# SparkX-Pi-Filter.net
KiCad netlist of a schematic drawn in EAGLE
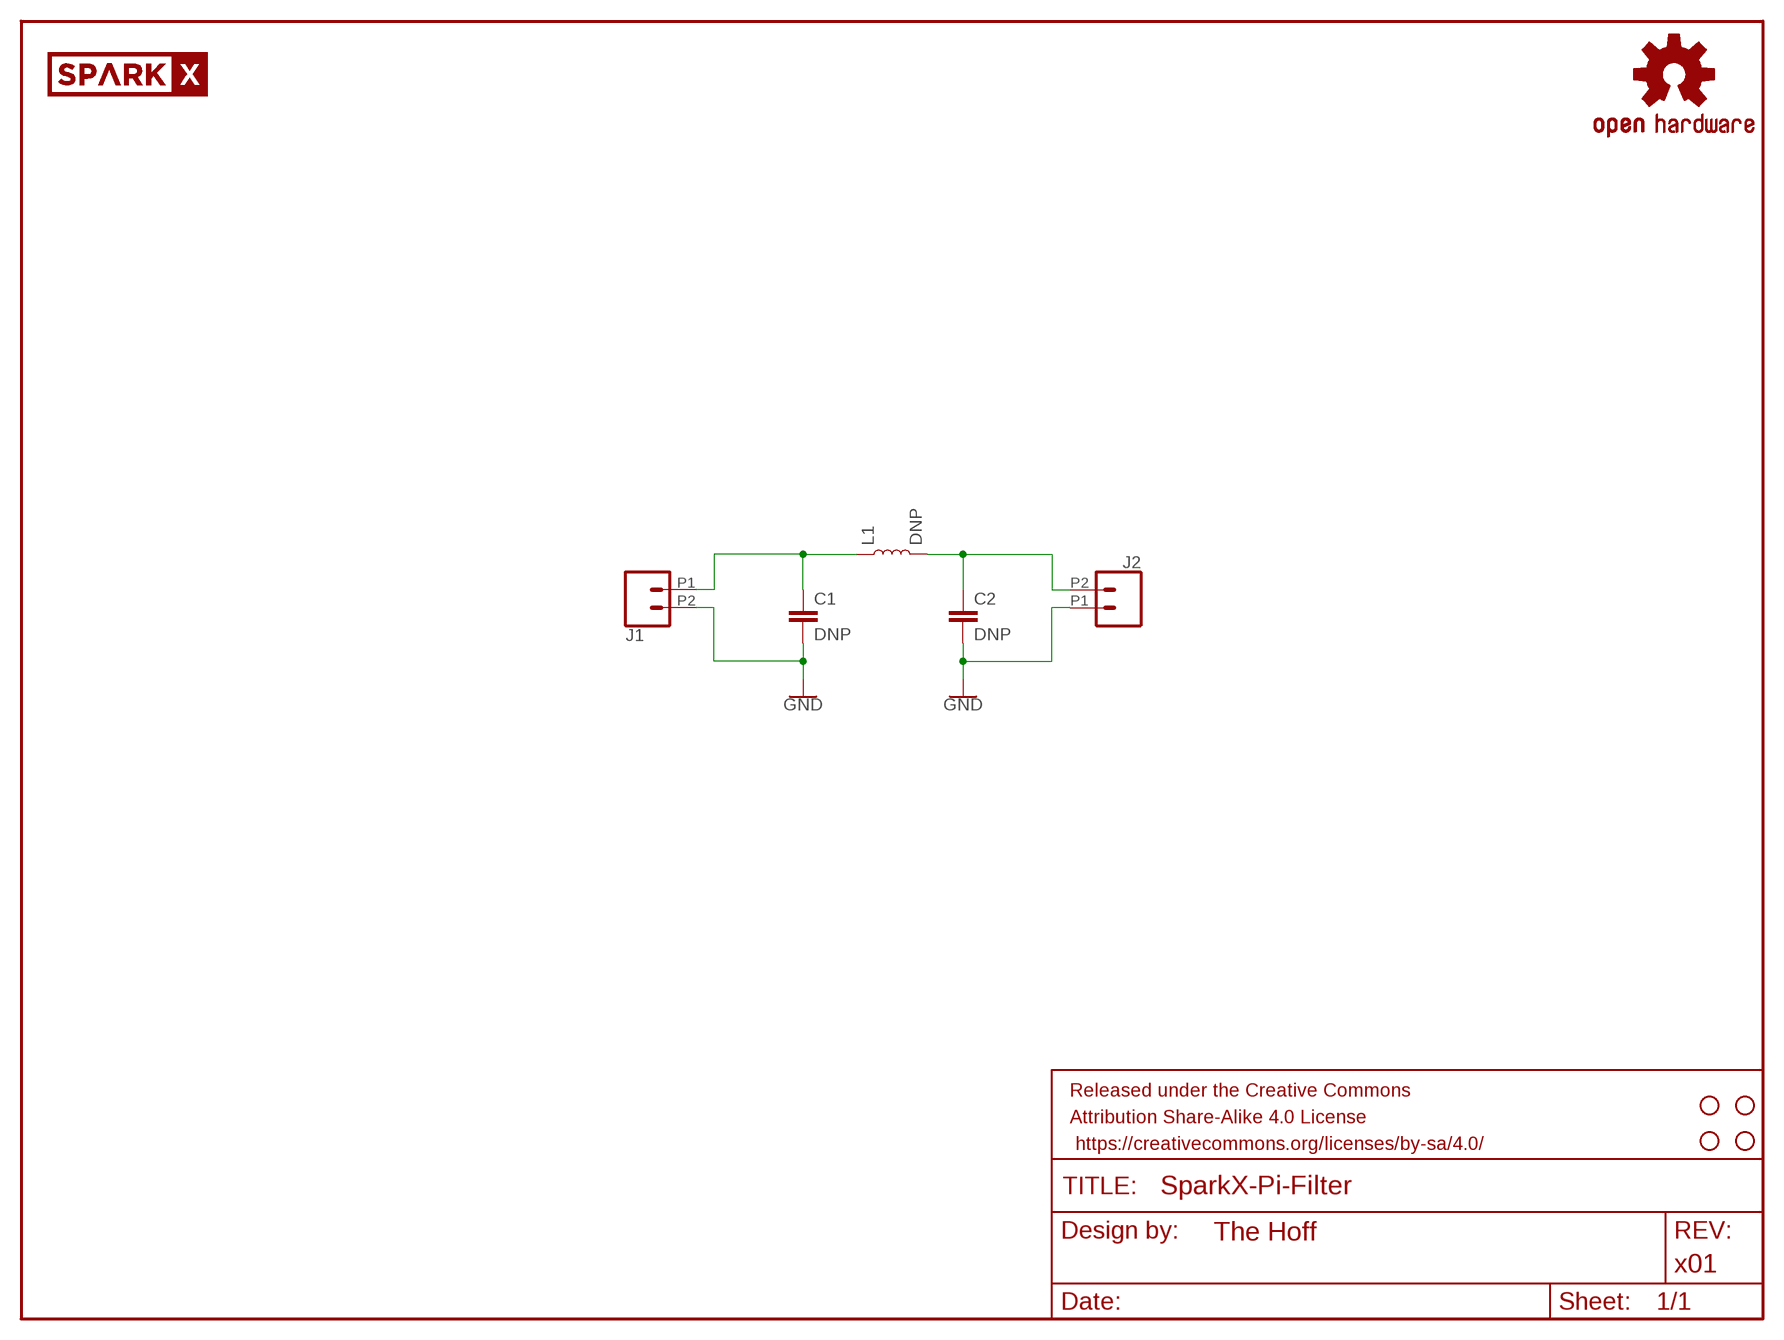
[diagram p0: schematic, sheet 1]

(export (version "E")
  (design (tool "Eeschema 10.0.6"))
  (components
    (comp (ref "C1")
      (value "DNP")
      (footprint "eagle-import:0805")
      (libsource (lib "eagle-import") (part "1.0UF-0805-25V-(+80/-20%)"))
    )
    (comp (ref "C2")
      (value "DNP")
      (footprint "eagle-import:0805")
      (libsource (lib "eagle-import") (part "1.0UF-0805-25V-(+80/-20%)"))
    )
    (comp (ref "FRAME1")
      (value "FRAME-LETTER")
      (footprint "eagle-import:CREATIVE_COMMONS")
      (fields (field (name "DESIGNER") "The Hoff") (field (name "REV") "x01"))
      (libsource (lib "eagle-import") (part "FRAME-LETTER"))
    )
    (comp (ref "H1")
      (value "STAND-OFF")
      (footprint "eagle-import:STAND-OFF")
      (libsource (lib "eagle-import") (part "STAND-OFF"))
    )
    (comp (ref "H2")
      (value "STAND-OFF")
      (footprint "eagle-import:STAND-OFF")
      (libsource (lib "eagle-import") (part "STAND-OFF"))
    )
    (comp (ref "H3")
      (value "STAND-OFF")
      (footprint "eagle-import:STAND-OFF")
      (libsource (lib "eagle-import") (part "STAND-OFF"))
    )
    (comp (ref "H4")
      (value "STAND-OFF")
      (footprint "eagle-import:STAND-OFF")
      (libsource (lib "eagle-import") (part "STAND-OFF"))
    )
    (comp (ref "J1")
      (value "CONN_022.54MM_SCREWTERM")
      (footprint "eagle-import:1X02_2.54_SCREWTERM")
      (libsource (lib "eagle-import") (part "CONN_022.54MM_SCREWTERM"))
    )
    (comp (ref "J2")
      (value "CONN_022.54MM_SCREWTERM")
      (footprint "eagle-import:1X02_2.54_SCREWTERM")
      (libsource (lib "eagle-import") (part "CONN_022.54MM_SCREWTERM"))
    )
    (comp (ref "L1")
      (value "DNP")
      (footprint "eagle-import:0805")
      (libsource (lib "eagle-import") (part "INDUCTOR-0805-3.3UH"))
    )
    (comp (ref "LOGO1")
      (value "OSHW-LOGOM")
      (footprint "eagle-import:OSHW-LOGO-M")
      (libsource (lib "eagle-import") (part "OSHW-LOGOM"))
    )
    (comp (ref "U$1")
      (value "SPARKX-LOGO4")
      (footprint "eagle-import:SPARKX-MEDIUM")
      (libsource (lib "eagle-import") (part "SPARKX-LOGO4"))
    )
  )
  (nets
    (net (code "1") (name "GND") (class "Default")
      (node (ref "C1") (pin "2") (pinfunction "2_2") (pintype "passive"))
      (node (ref "C2") (pin "2") (pinfunction "2_2") (pintype "passive"))
      (node (ref "J1") (pin "P2") (pinfunction "2_P2") (pintype "passive"))
      (node (ref "J2") (pin "P1") (pinfunction "1_P1") (pintype "passive"))
    )
    (net (code "2") (name "Net-(J1-1)") (class "Default")
      (node (ref "C1") (pin "1") (pinfunction "1_1") (pintype "passive"))
      (node (ref "J1") (pin "P1") (pinfunction "1_P1") (pintype "passive"))
      (node (ref "L1") (pin "1") (pinfunction "1_1") (pintype "passive"))
    )
    (net (code "3") (name "Net-(J2-2)") (class "Default")
      (node (ref "C2") (pin "1") (pinfunction "1_1") (pintype "passive"))
      (node (ref "J2") (pin "P2") (pinfunction "2_P2") (pintype "passive"))
      (node (ref "L1") (pin "2") (pinfunction "2_2") (pintype "passive"))
    )
  )
)
